# Display_Board.net
KiCad netlist of a schematic drawn in EAGLE
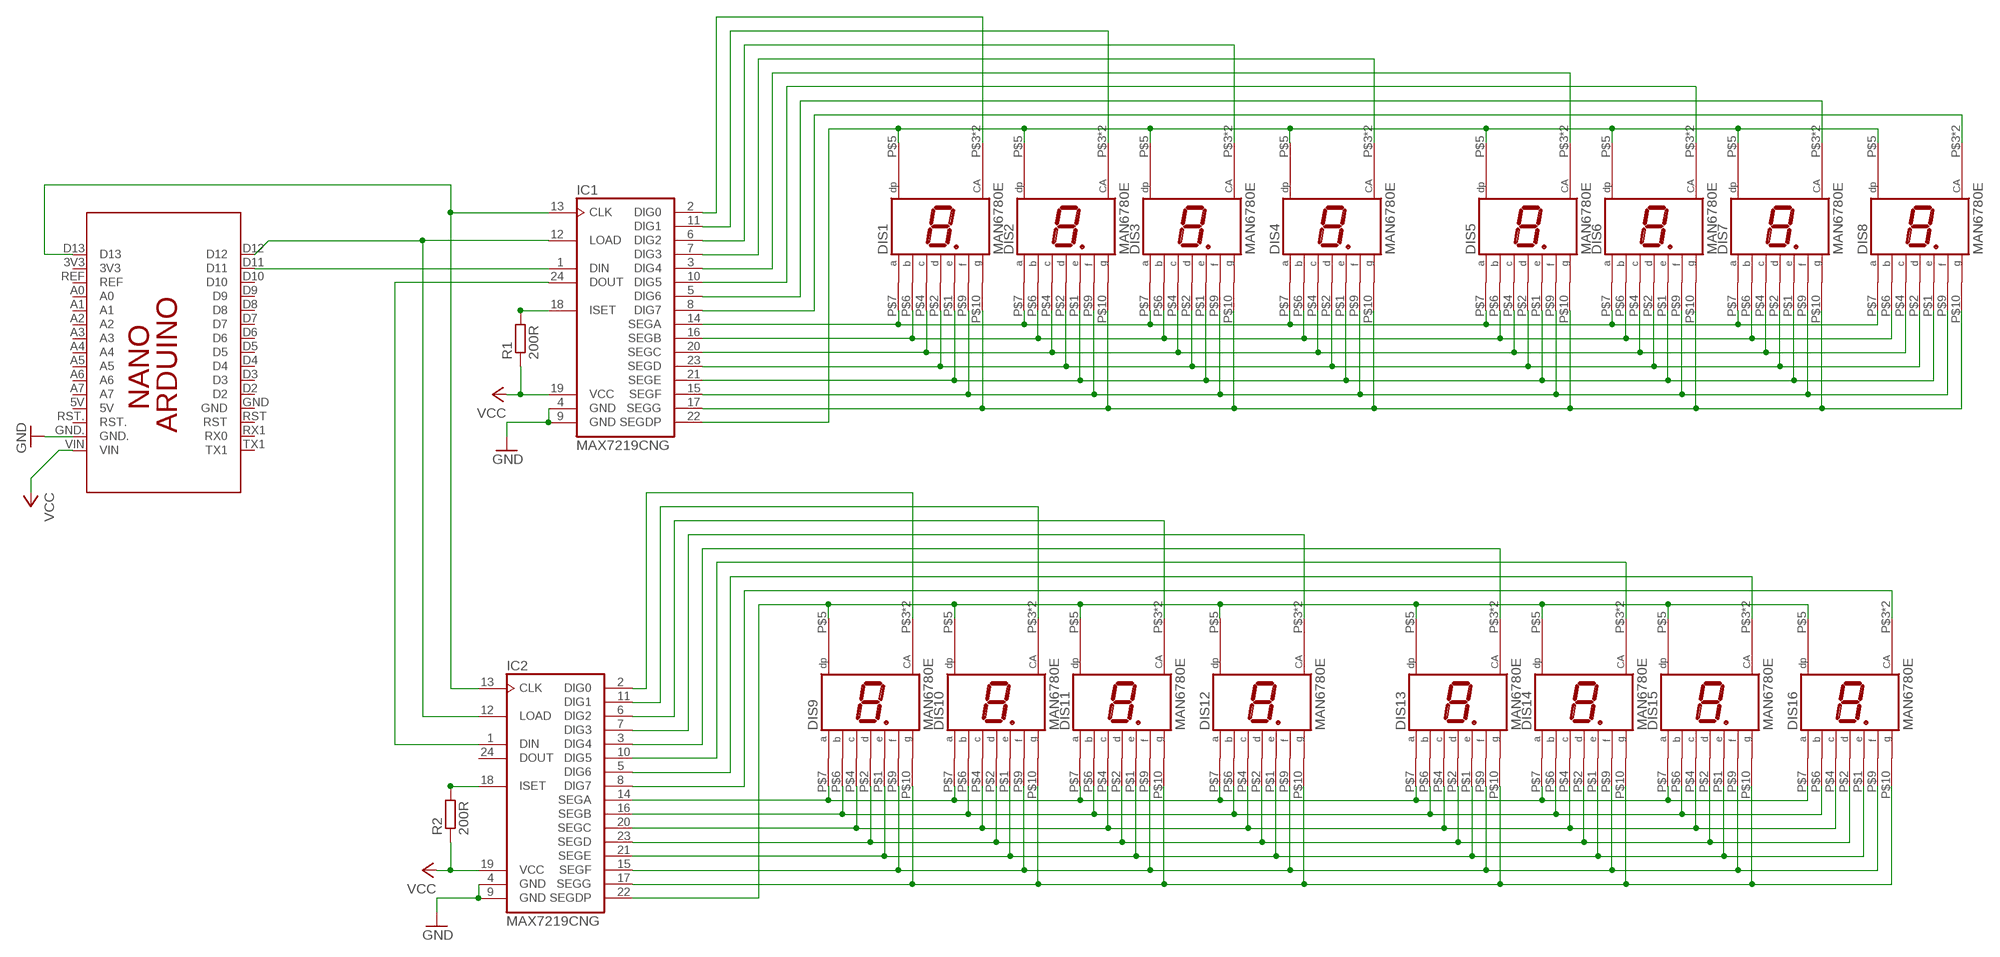
[diagram p0: schematic, sheet 1]

(export (version "E")
  (design (tool "Eeschema 10.0.6"))
  (components
    (comp (ref "DIS1")
      (value "MAN6780E")
      (footprint "eagle-import:MAN6780")
      (libsource (lib "eagle-import") (part "MAN6780E"))
    )
    (comp (ref "DIS2")
      (value "MAN6780E")
      (footprint "eagle-import:MAN6780")
      (libsource (lib "eagle-import") (part "MAN6780E"))
    )
    (comp (ref "DIS3")
      (value "MAN6780E")
      (footprint "eagle-import:MAN6780")
      (libsource (lib "eagle-import") (part "MAN6780E"))
    )
    (comp (ref "DIS4")
      (value "MAN6780E")
      (footprint "eagle-import:MAN6780")
      (libsource (lib "eagle-import") (part "MAN6780E"))
    )
    (comp (ref "DIS5")
      (value "MAN6780E")
      (footprint "eagle-import:MAN6780")
      (libsource (lib "eagle-import") (part "MAN6780E"))
    )
    (comp (ref "DIS6")
      (value "MAN6780E")
      (footprint "eagle-import:MAN6780")
      (libsource (lib "eagle-import") (part "MAN6780E"))
    )
    (comp (ref "DIS7")
      (value "MAN6780E")
      (footprint "eagle-import:MAN6780")
      (libsource (lib "eagle-import") (part "MAN6780E"))
    )
    (comp (ref "DIS8")
      (value "MAN6780E")
      (footprint "eagle-import:MAN6780")
      (libsource (lib "eagle-import") (part "MAN6780E"))
    )
    (comp (ref "DIS9")
      (value "MAN6780E")
      (footprint "eagle-import:MAN6780")
      (libsource (lib "eagle-import") (part "MAN6780E"))
    )
    (comp (ref "DIS10")
      (value "MAN6780E")
      (footprint "eagle-import:MAN6780")
      (libsource (lib "eagle-import") (part "MAN6780E"))
    )
    (comp (ref "DIS11")
      (value "MAN6780E")
      (footprint "eagle-import:MAN6780")
      (libsource (lib "eagle-import") (part "MAN6780E"))
    )
    (comp (ref "DIS12")
      (value "MAN6780E")
      (footprint "eagle-import:MAN6780")
      (libsource (lib "eagle-import") (part "MAN6780E"))
    )
    (comp (ref "DIS13")
      (value "MAN6780E")
      (footprint "eagle-import:MAN6780")
      (libsource (lib "eagle-import") (part "MAN6780E"))
    )
    (comp (ref "DIS14")
      (value "MAN6780E")
      (footprint "eagle-import:MAN6780")
      (libsource (lib "eagle-import") (part "MAN6780E"))
    )
    (comp (ref "DIS15")
      (value "MAN6780E")
      (footprint "eagle-import:MAN6780")
      (libsource (lib "eagle-import") (part "MAN6780E"))
    )
    (comp (ref "DIS16")
      (value "MAN6780E")
      (footprint "eagle-import:MAN6780")
      (libsource (lib "eagle-import") (part "MAN6780E"))
    )
    (comp (ref "IC1")
      (value "MAX7219CNG")
      (footprint "eagle-import:DIL24-3")
      (fields (field (name "MF") "MAXIM"))
      (libsource (lib "eagle-import") (part "MAX7219CNG"))
    )
    (comp (ref "IC2")
      (value "MAX7219CNG")
      (footprint "eagle-import:DIL24-3")
      (fields (field (name "MF") "MAXIM"))
      (libsource (lib "eagle-import") (part "MAX7219CNG"))
    )
    (comp (ref "PCB1")
      (value "ARDUINO_NANO")
      (footprint "eagle-import:ARDUINO_NANO")
      (libsource (lib "eagle-import") (part "ARDUINO_NANO"))
    )
    (comp (ref "R1")
      (value "200R")
      (footprint "eagle-import:M1206")
      (libsource (lib "eagle-import") (part "R-EU_M1206"))
    )
    (comp (ref "R2")
      (value "200R")
      (footprint "eagle-import:M1206")
      (libsource (lib "eagle-import") (part "R-EU_M1206"))
    )
  )
  (nets
    (net (code "1") (name "GND") (class "Default")
      (node (ref "IC1") (pin "4") (pinfunction "GND_4") (pintype "power_in"))
      (node (ref "IC1") (pin "9") (pinfunction "GND_9") (pintype "power_in"))
      (node (ref "IC2") (pin "4") (pinfunction "GND_4") (pintype "power_in"))
      (node (ref "IC2") (pin "9") (pinfunction "GND_9") (pintype "power_in"))
      (node (ref "PCB1") (pin "GND.") (pinfunction "GND._GND.") (pintype "bidirectional"))
    )
    (net (code "2") (name "Net-(DIS1-A)") (class "Default")
      (node (ref "DIS1") (pin "P$7") (pinfunction "A_P$7") (pintype "passive"))
      (node (ref "DIS2") (pin "P$7") (pinfunction "A_P$7") (pintype "passive"))
      (node (ref "DIS3") (pin "P$7") (pinfunction "A_P$7") (pintype "passive"))
      (node (ref "DIS4") (pin "P$7") (pinfunction "A_P$7") (pintype "passive"))
      (node (ref "DIS5") (pin "P$7") (pinfunction "A_P$7") (pintype "passive"))
      (node (ref "DIS6") (pin "P$7") (pinfunction "A_P$7") (pintype "passive"))
      (node (ref "DIS7") (pin "P$7") (pinfunction "A_P$7") (pintype "passive"))
      (node (ref "DIS8") (pin "P$7") (pinfunction "A_P$7") (pintype "passive"))
      (node (ref "IC1") (pin "14") (pinfunction "SEGA_14") (pintype "output"))
    )
    (net (code "3") (name "Net-(DIS1-B)") (class "Default")
      (node (ref "DIS1") (pin "P$6") (pinfunction "B_P$6") (pintype "passive"))
      (node (ref "DIS2") (pin "P$6") (pinfunction "B_P$6") (pintype "passive"))
      (node (ref "DIS3") (pin "P$6") (pinfunction "B_P$6") (pintype "passive"))
      (node (ref "DIS4") (pin "P$6") (pinfunction "B_P$6") (pintype "passive"))
      (node (ref "DIS5") (pin "P$6") (pinfunction "B_P$6") (pintype "passive"))
      (node (ref "DIS6") (pin "P$6") (pinfunction "B_P$6") (pintype "passive"))
      (node (ref "DIS7") (pin "P$6") (pinfunction "B_P$6") (pintype "passive"))
      (node (ref "DIS8") (pin "P$6") (pinfunction "B_P$6") (pintype "passive"))
      (node (ref "IC1") (pin "16") (pinfunction "SEGB_16") (pintype "output"))
    )
    (net (code "4") (name "Net-(DIS1-C)") (class "Default")
      (node (ref "DIS1") (pin "P$4") (pinfunction "C_P$4") (pintype "passive"))
      (node (ref "DIS2") (pin "P$4") (pinfunction "C_P$4") (pintype "passive"))
      (node (ref "DIS3") (pin "P$4") (pinfunction "C_P$4") (pintype "passive"))
      (node (ref "DIS4") (pin "P$4") (pinfunction "C_P$4") (pintype "passive"))
      (node (ref "DIS5") (pin "P$4") (pinfunction "C_P$4") (pintype "passive"))
      (node (ref "DIS6") (pin "P$4") (pinfunction "C_P$4") (pintype "passive"))
      (node (ref "DIS7") (pin "P$4") (pinfunction "C_P$4") (pintype "passive"))
      (node (ref "DIS8") (pin "P$4") (pinfunction "C_P$4") (pintype "passive"))
      (node (ref "IC1") (pin "20") (pinfunction "SEGC_20") (pintype "output"))
    )
    (net (code "5") (name "Net-(DIS1-D)") (class "Default")
      (node (ref "DIS1") (pin "P$2") (pinfunction "D_P$2") (pintype "passive"))
      (node (ref "DIS2") (pin "P$2") (pinfunction "D_P$2") (pintype "passive"))
      (node (ref "DIS3") (pin "P$2") (pinfunction "D_P$2") (pintype "passive"))
      (node (ref "DIS4") (pin "P$2") (pinfunction "D_P$2") (pintype "passive"))
      (node (ref "DIS5") (pin "P$2") (pinfunction "D_P$2") (pintype "passive"))
      (node (ref "DIS6") (pin "P$2") (pinfunction "D_P$2") (pintype "passive"))
      (node (ref "DIS7") (pin "P$2") (pinfunction "D_P$2") (pintype "passive"))
      (node (ref "DIS8") (pin "P$2") (pinfunction "D_P$2") (pintype "passive"))
      (node (ref "IC1") (pin "23") (pinfunction "SEGD_23") (pintype "output"))
    )
    (net (code "6") (name "Net-(DIS1-DP)") (class "Default")
      (node (ref "DIS1") (pin "P$5") (pinfunction "DP_P$5") (pintype "passive"))
      (node (ref "DIS2") (pin "P$5") (pinfunction "DP_P$5") (pintype "passive"))
      (node (ref "DIS3") (pin "P$5") (pinfunction "DP_P$5") (pintype "passive"))
      (node (ref "DIS4") (pin "P$5") (pinfunction "DP_P$5") (pintype "passive"))
      (node (ref "DIS5") (pin "P$5") (pinfunction "DP_P$5") (pintype "passive"))
      (node (ref "DIS6") (pin "P$5") (pinfunction "DP_P$5") (pintype "passive"))
      (node (ref "DIS7") (pin "P$5") (pinfunction "DP_P$5") (pintype "passive"))
      (node (ref "DIS8") (pin "P$5") (pinfunction "DP_P$5") (pintype "passive"))
      (node (ref "IC1") (pin "22") (pinfunction "SEGDP_22") (pintype "output"))
    )
    (net (code "7") (name "Net-(DIS1-E)") (class "Default")
      (node (ref "DIS1") (pin "P$1") (pinfunction "E_P$1") (pintype "passive"))
      (node (ref "DIS2") (pin "P$1") (pinfunction "E_P$1") (pintype "passive"))
      (node (ref "DIS3") (pin "P$1") (pinfunction "E_P$1") (pintype "passive"))
      (node (ref "DIS4") (pin "P$1") (pinfunction "E_P$1") (pintype "passive"))
      (node (ref "DIS5") (pin "P$1") (pinfunction "E_P$1") (pintype "passive"))
      (node (ref "DIS6") (pin "P$1") (pinfunction "E_P$1") (pintype "passive"))
      (node (ref "DIS7") (pin "P$1") (pinfunction "E_P$1") (pintype "passive"))
      (node (ref "DIS8") (pin "P$1") (pinfunction "E_P$1") (pintype "passive"))
      (node (ref "IC1") (pin "21") (pinfunction "SEGE_21") (pintype "output"))
    )
    (net (code "8") (name "Net-(DIS1-F)") (class "Default")
      (node (ref "DIS1") (pin "P$9") (pinfunction "F_P$9") (pintype "passive"))
      (node (ref "DIS2") (pin "P$9") (pinfunction "F_P$9") (pintype "passive"))
      (node (ref "DIS3") (pin "P$9") (pinfunction "F_P$9") (pintype "passive"))
      (node (ref "DIS4") (pin "P$9") (pinfunction "F_P$9") (pintype "passive"))
      (node (ref "DIS5") (pin "P$9") (pinfunction "F_P$9") (pintype "passive"))
      (node (ref "DIS6") (pin "P$9") (pinfunction "F_P$9") (pintype "passive"))
      (node (ref "DIS7") (pin "P$9") (pinfunction "F_P$9") (pintype "passive"))
      (node (ref "DIS8") (pin "P$9") (pinfunction "F_P$9") (pintype "passive"))
      (node (ref "IC1") (pin "15") (pinfunction "SEGF_15") (pintype "output"))
    )
    (net (code "9") (name "Net-(DIS1-G)") (class "Default")
      (node (ref "DIS1") (pin "P$10") (pinfunction "G_P$10") (pintype "passive"))
      (node (ref "DIS2") (pin "P$10") (pinfunction "G_P$10") (pintype "passive"))
      (node (ref "DIS3") (pin "P$10") (pinfunction "G_P$10") (pintype "passive"))
      (node (ref "DIS4") (pin "P$10") (pinfunction "G_P$10") (pintype "passive"))
      (node (ref "DIS5") (pin "P$10") (pinfunction "G_P$10") (pintype "passive"))
      (node (ref "DIS6") (pin "P$10") (pinfunction "G_P$10") (pintype "passive"))
      (node (ref "DIS7") (pin "P$10") (pinfunction "G_P$10") (pintype "passive"))
      (node (ref "DIS8") (pin "P$10") (pinfunction "G_P$10") (pintype "passive"))
      (node (ref "IC1") (pin "17") (pinfunction "SEGG_17") (pintype "output"))
    )
    (net (code "10") (name "Net-(DIS10-A)") (class "Default")
      (node (ref "DIS10") (pin "P$7") (pinfunction "A_P$7") (pintype "passive"))
      (node (ref "DIS11") (pin "P$7") (pinfunction "A_P$7") (pintype "passive"))
      (node (ref "DIS12") (pin "P$7") (pinfunction "A_P$7") (pintype "passive"))
      (node (ref "DIS13") (pin "P$7") (pinfunction "A_P$7") (pintype "passive"))
      (node (ref "DIS14") (pin "P$7") (pinfunction "A_P$7") (pintype "passive"))
      (node (ref "DIS15") (pin "P$7") (pinfunction "A_P$7") (pintype "passive"))
      (node (ref "DIS16") (pin "P$7") (pinfunction "A_P$7") (pintype "passive"))
      (node (ref "DIS9") (pin "P$7") (pinfunction "A_P$7") (pintype "passive"))
      (node (ref "IC2") (pin "14") (pinfunction "SEGA_14") (pintype "output"))
    )
    (net (code "11") (name "Net-(DIS10-B)") (class "Default")
      (node (ref "DIS10") (pin "P$6") (pinfunction "B_P$6") (pintype "passive"))
      (node (ref "DIS11") (pin "P$6") (pinfunction "B_P$6") (pintype "passive"))
      (node (ref "DIS12") (pin "P$6") (pinfunction "B_P$6") (pintype "passive"))
      (node (ref "DIS13") (pin "P$6") (pinfunction "B_P$6") (pintype "passive"))
      (node (ref "DIS14") (pin "P$6") (pinfunction "B_P$6") (pintype "passive"))
      (node (ref "DIS15") (pin "P$6") (pinfunction "B_P$6") (pintype "passive"))
      (node (ref "DIS16") (pin "P$6") (pinfunction "B_P$6") (pintype "passive"))
      (node (ref "DIS9") (pin "P$6") (pinfunction "B_P$6") (pintype "passive"))
      (node (ref "IC2") (pin "16") (pinfunction "SEGB_16") (pintype "output"))
    )
    (net (code "12") (name "Net-(DIS10-C)") (class "Default")
      (node (ref "DIS10") (pin "P$4") (pinfunction "C_P$4") (pintype "passive"))
      (node (ref "DIS11") (pin "P$4") (pinfunction "C_P$4") (pintype "passive"))
      (node (ref "DIS12") (pin "P$4") (pinfunction "C_P$4") (pintype "passive"))
      (node (ref "DIS13") (pin "P$4") (pinfunction "C_P$4") (pintype "passive"))
      (node (ref "DIS14") (pin "P$4") (pinfunction "C_P$4") (pintype "passive"))
      (node (ref "DIS15") (pin "P$4") (pinfunction "C_P$4") (pintype "passive"))
      (node (ref "DIS16") (pin "P$4") (pinfunction "C_P$4") (pintype "passive"))
      (node (ref "DIS9") (pin "P$4") (pinfunction "C_P$4") (pintype "passive"))
      (node (ref "IC2") (pin "20") (pinfunction "SEGC_20") (pintype "output"))
    )
    (net (code "13") (name "Net-(DIS10-D)") (class "Default")
      (node (ref "DIS10") (pin "P$2") (pinfunction "D_P$2") (pintype "passive"))
      (node (ref "DIS11") (pin "P$2") (pinfunction "D_P$2") (pintype "passive"))
      (node (ref "DIS12") (pin "P$2") (pinfunction "D_P$2") (pintype "passive"))
      (node (ref "DIS13") (pin "P$2") (pinfunction "D_P$2") (pintype "passive"))
      (node (ref "DIS14") (pin "P$2") (pinfunction "D_P$2") (pintype "passive"))
      (node (ref "DIS15") (pin "P$2") (pinfunction "D_P$2") (pintype "passive"))
      (node (ref "DIS16") (pin "P$2") (pinfunction "D_P$2") (pintype "passive"))
      (node (ref "DIS9") (pin "P$2") (pinfunction "D_P$2") (pintype "passive"))
      (node (ref "IC2") (pin "23") (pinfunction "SEGD_23") (pintype "output"))
    )
    (net (code "14") (name "Net-(DIS10-DP)") (class "Default")
      (node (ref "DIS10") (pin "P$5") (pinfunction "DP_P$5") (pintype "passive"))
      (node (ref "DIS11") (pin "P$5") (pinfunction "DP_P$5") (pintype "passive"))
      (node (ref "DIS12") (pin "P$5") (pinfunction "DP_P$5") (pintype "passive"))
      (node (ref "DIS13") (pin "P$5") (pinfunction "DP_P$5") (pintype "passive"))
      (node (ref "DIS14") (pin "P$5") (pinfunction "DP_P$5") (pintype "passive"))
      (node (ref "DIS15") (pin "P$5") (pinfunction "DP_P$5") (pintype "passive"))
      (node (ref "DIS16") (pin "P$5") (pinfunction "DP_P$5") (pintype "passive"))
      (node (ref "DIS9") (pin "P$5") (pinfunction "DP_P$5") (pintype "passive"))
      (node (ref "IC2") (pin "22") (pinfunction "SEGDP_22") (pintype "output"))
    )
    (net (code "15") (name "Net-(DIS10-E)") (class "Default")
      (node (ref "DIS10") (pin "P$1") (pinfunction "E_P$1") (pintype "passive"))
      (node (ref "DIS11") (pin "P$1") (pinfunction "E_P$1") (pintype "passive"))
      (node (ref "DIS12") (pin "P$1") (pinfunction "E_P$1") (pintype "passive"))
      (node (ref "DIS13") (pin "P$1") (pinfunction "E_P$1") (pintype "passive"))
      (node (ref "DIS14") (pin "P$1") (pinfunction "E_P$1") (pintype "passive"))
      (node (ref "DIS15") (pin "P$1") (pinfunction "E_P$1") (pintype "passive"))
      (node (ref "DIS16") (pin "P$1") (pinfunction "E_P$1") (pintype "passive"))
      (node (ref "DIS9") (pin "P$1") (pinfunction "E_P$1") (pintype "passive"))
      (node (ref "IC2") (pin "21") (pinfunction "SEGE_21") (pintype "output"))
    )
    (net (code "16") (name "Net-(DIS10-F)") (class "Default")
      (node (ref "DIS10") (pin "P$9") (pinfunction "F_P$9") (pintype "passive"))
      (node (ref "DIS11") (pin "P$9") (pinfunction "F_P$9") (pintype "passive"))
      (node (ref "DIS12") (pin "P$9") (pinfunction "F_P$9") (pintype "passive"))
      (node (ref "DIS13") (pin "P$9") (pinfunction "F_P$9") (pintype "passive"))
      (node (ref "DIS14") (pin "P$9") (pinfunction "F_P$9") (pintype "passive"))
      (node (ref "DIS15") (pin "P$9") (pinfunction "F_P$9") (pintype "passive"))
      (node (ref "DIS16") (pin "P$9") (pinfunction "F_P$9") (pintype "passive"))
      (node (ref "DIS9") (pin "P$9") (pinfunction "F_P$9") (pintype "passive"))
      (node (ref "IC2") (pin "15") (pinfunction "SEGF_15") (pintype "output"))
    )
    (net (code "17") (name "Net-(DIS10-G)") (class "Default")
      (node (ref "DIS10") (pin "P$10") (pinfunction "G_P$10") (pintype "passive"))
      (node (ref "DIS11") (pin "P$10") (pinfunction "G_P$10") (pintype "passive"))
      (node (ref "DIS12") (pin "P$10") (pinfunction "G_P$10") (pintype "passive"))
      (node (ref "DIS13") (pin "P$10") (pinfunction "G_P$10") (pintype "passive"))
      (node (ref "DIS14") (pin "P$10") (pinfunction "G_P$10") (pintype "passive"))
      (node (ref "DIS15") (pin "P$10") (pinfunction "G_P$10") (pintype "passive"))
      (node (ref "DIS16") (pin "P$10") (pinfunction "G_P$10") (pintype "passive"))
      (node (ref "DIS9") (pin "P$10") (pinfunction "G_P$10") (pintype "passive"))
      (node (ref "IC2") (pin "17") (pinfunction "SEGG_17") (pintype "output"))
    )
    (net (code "18") (name "Net-(IC1-CLK)") (class "Default")
      (node (ref "IC1") (pin "13") (pinfunction "CLK_13") (pintype "input"))
      (node (ref "IC2") (pin "13") (pinfunction "CLK_13") (pintype "input"))
      (node (ref "PCB1") (pin "D13") (pinfunction "D13_D13") (pintype "bidirectional"))
    )
    (net (code "19") (name "Net-(IC1-DIG0)") (class "Default")
      (node (ref "DIS1") (pin "P$3") (pinfunction "CA_P$3") (pintype "passive"))
      (node (ref "DIS1") (pin "P$8") (pinfunction "CA_P$8") (pintype "passive"))
      (node (ref "IC1") (pin "2") (pinfunction "DIG0_2") (pintype "output"))
    )
    (net (code "20") (name "Net-(IC1-DIG1)") (class "Default")
      (node (ref "DIS2") (pin "P$3") (pinfunction "CA_P$3") (pintype "passive"))
      (node (ref "DIS2") (pin "P$8") (pinfunction "CA_P$8") (pintype "passive"))
      (node (ref "IC1") (pin "11") (pinfunction "DIG1_11") (pintype "output"))
    )
    (net (code "21") (name "Net-(IC1-DIG2)") (class "Default")
      (node (ref "DIS3") (pin "P$3") (pinfunction "CA_P$3") (pintype "passive"))
      (node (ref "DIS3") (pin "P$8") (pinfunction "CA_P$8") (pintype "passive"))
      (node (ref "IC1") (pin "6") (pinfunction "DIG2_6") (pintype "output"))
    )
    (net (code "22") (name "Net-(IC1-DIG3)") (class "Default")
      (node (ref "DIS4") (pin "P$3") (pinfunction "CA_P$3") (pintype "passive"))
      (node (ref "DIS4") (pin "P$8") (pinfunction "CA_P$8") (pintype "passive"))
      (node (ref "IC1") (pin "7") (pinfunction "DIG3_7") (pintype "output"))
    )
    (net (code "23") (name "Net-(IC1-DIG4)") (class "Default")
      (node (ref "DIS5") (pin "P$3") (pinfunction "CA_P$3") (pintype "passive"))
      (node (ref "DIS5") (pin "P$8") (pinfunction "CA_P$8") (pintype "passive"))
      (node (ref "IC1") (pin "3") (pinfunction "DIG4_3") (pintype "output"))
    )
    (net (code "24") (name "Net-(IC1-DIG5)") (class "Default")
      (node (ref "DIS6") (pin "P$3") (pinfunction "CA_P$3") (pintype "passive"))
      (node (ref "DIS6") (pin "P$8") (pinfunction "CA_P$8") (pintype "passive"))
      (node (ref "IC1") (pin "10") (pinfunction "DIG5_10") (pintype "output"))
    )
    (net (code "25") (name "Net-(IC1-DIG6)") (class "Default")
      (node (ref "DIS7") (pin "P$3") (pinfunction "CA_P$3") (pintype "passive"))
      (node (ref "DIS7") (pin "P$8") (pinfunction "CA_P$8") (pintype "passive"))
      (node (ref "IC1") (pin "5") (pinfunction "DIG6_5") (pintype "output"))
    )
    (net (code "26") (name "Net-(IC1-DIG7)") (class "Default")
      (node (ref "DIS8") (pin "P$3") (pinfunction "CA_P$3") (pintype "passive"))
      (node (ref "DIS8") (pin "P$8") (pinfunction "CA_P$8") (pintype "passive"))
      (node (ref "IC1") (pin "8") (pinfunction "DIG7_8") (pintype "output"))
    )
    (net (code "27") (name "Net-(IC1-DIN)") (class "Default")
      (node (ref "IC1") (pin "1") (pinfunction "DIN_1") (pintype "input"))
      (node (ref "PCB1") (pin "D11") (pinfunction "D11_D11") (pintype "bidirectional"))
    )
    (net (code "28") (name "Net-(IC1-DOUT)") (class "Default")
      (node (ref "IC1") (pin "24") (pinfunction "DOUT_24") (pintype "output"))
      (node (ref "IC2") (pin "1") (pinfunction "DIN_1") (pintype "input"))
    )
    (net (code "29") (name "Net-(IC1-ISET)") (class "Default")
      (node (ref "IC1") (pin "18") (pinfunction "ISET_18") (pintype "input"))
      (node (ref "R1") (pin "2") (pinfunction "2_2") (pintype "passive"))
    )
    (net (code "30") (name "Net-(IC1-LOAD)") (class "Default")
      (node (ref "IC1") (pin "12") (pinfunction "LOAD_12") (pintype "input"))
      (node (ref "IC2") (pin "12") (pinfunction "LOAD_12") (pintype "input"))
      (node (ref "PCB1") (pin "D12") (pinfunction "D12_D12") (pintype "bidirectional"))
    )
    (net (code "31") (name "Net-(IC2-DIG0)") (class "Default")
      (node (ref "DIS9") (pin "P$3") (pinfunction "CA_P$3") (pintype "passive"))
      (node (ref "DIS9") (pin "P$8") (pinfunction "CA_P$8") (pintype "passive"))
      (node (ref "IC2") (pin "2") (pinfunction "DIG0_2") (pintype "output"))
    )
    (net (code "32") (name "Net-(IC2-DIG1)") (class "Default")
      (node (ref "DIS10") (pin "P$3") (pinfunction "CA_P$3") (pintype "passive"))
      (node (ref "DIS10") (pin "P$8") (pinfunction "CA_P$8") (pintype "passive"))
      (node (ref "IC2") (pin "11") (pinfunction "DIG1_11") (pintype "output"))
    )
    (net (code "33") (name "Net-(IC2-DIG2)") (class "Default")
      (node (ref "DIS11") (pin "P$3") (pinfunction "CA_P$3") (pintype "passive"))
      (node (ref "DIS11") (pin "P$8") (pinfunction "CA_P$8") (pintype "passive"))
      (node (ref "IC2") (pin "6") (pinfunction "DIG2_6") (pintype "output"))
    )
    (net (code "34") (name "Net-(IC2-DIG3)") (class "Default")
      (node (ref "DIS12") (pin "P$3") (pinfunction "CA_P$3") (pintype "passive"))
      (node (ref "DIS12") (pin "P$8") (pinfunction "CA_P$8") (pintype "passive"))
      (node (ref "IC2") (pin "7") (pinfunction "DIG3_7") (pintype "output"))
    )
    (net (code "35") (name "Net-(IC2-DIG4)") (class "Default")
      (node (ref "DIS13") (pin "P$3") (pinfunction "CA_P$3") (pintype "passive"))
      (node (ref "DIS13") (pin "P$8") (pinfunction "CA_P$8") (pintype "passive"))
      (node (ref "IC2") (pin "3") (pinfunction "DIG4_3") (pintype "output"))
    )
    (net (code "36") (name "Net-(IC2-DIG5)") (class "Default")
      (node (ref "DIS14") (pin "P$3") (pinfunction "CA_P$3") (pintype "passive"))
      (node (ref "DIS14") (pin "P$8") (pinfunction "CA_P$8") (pintype "passive"))
      (node (ref "IC2") (pin "10") (pinfunction "DIG5_10") (pintype "output"))
    )
    (net (code "37") (name "Net-(IC2-DIG6)") (class "Default")
      (node (ref "DIS15") (pin "P$3") (pinfunction "CA_P$3") (pintype "passive"))
      (node (ref "DIS15") (pin "P$8") (pinfunction "CA_P$8") (pintype "passive"))
      (node (ref "IC2") (pin "5") (pinfunction "DIG6_5") (pintype "output"))
    )
    (net (code "38") (name "Net-(IC2-DIG7)") (class "Default")
      (node (ref "DIS16") (pin "P$3") (pinfunction "CA_P$3") (pintype "passive"))
      (node (ref "DIS16") (pin "P$8") (pinfunction "CA_P$8") (pintype "passive"))
      (node (ref "IC2") (pin "8") (pinfunction "DIG7_8") (pintype "output"))
    )
    (net (code "39") (name "Net-(IC2-ISET)") (class "Default")
      (node (ref "IC2") (pin "18") (pinfunction "ISET_18") (pintype "input"))
      (node (ref "R2") (pin "2") (pinfunction "2_2") (pintype "passive"))
    )
    (net (code "40") (name "VCC") (class "Default")
      (node (ref "IC1") (pin "19") (pinfunction "VCC_19") (pintype "power_in"))
      (node (ref "IC2") (pin "19") (pinfunction "VCC_19") (pintype "power_in"))
      (node (ref "PCB1") (pin "VIN") (pinfunction "VIN_VIN") (pintype "bidirectional"))
      (node (ref "R1") (pin "1") (pinfunction "1_1") (pintype "passive"))
      (node (ref "R2") (pin "1") (pinfunction "1_1") (pintype "passive"))
    )
    (net (code "41") (name "unconnected-(IC2-DOUT-Pad24)") (class "Default")
      (node (ref "IC2") (pin "24") (pinfunction "DOUT_24") (pintype "output"))
    )
    (net (code "42") (name "unconnected-(PCB1-Pad3V3)") (class "Default")
      (node (ref "PCB1") (pin "3V3") (pinfunction "3V3_3V3") (pintype "bidirectional"))
    )
    (net (code "43") (name "unconnected-(PCB1-Pad5V)") (class "Default")
      (node (ref "PCB1") (pin "5V") (pinfunction "5V_5V") (pintype "bidirectional"))
    )
    (net (code "44") (name "unconnected-(PCB1-PadA0)") (class "Default")
      (node (ref "PCB1") (pin "A0") (pinfunction "A0_A0") (pintype "bidirectional"))
    )
    (net (code "45") (name "unconnected-(PCB1-PadA1)") (class "Default")
      (node (ref "PCB1") (pin "A1") (pinfunction "A1_A1") (pintype "bidirectional"))
    )
    (net (code "46") (name "unconnected-(PCB1-PadA2)") (class "Default")
      (node (ref "PCB1") (pin "A2") (pinfunction "A2_A2") (pintype "bidirectional"))
    )
    (net (code "47") (name "unconnected-(PCB1-PadA3)") (class "Default")
      (node (ref "PCB1") (pin "A3") (pinfunction "A3_A3") (pintype "bidirectional"))
    )
    (net (code "48") (name "unconnected-(PCB1-PadA4)") (class "Default")
      (node (ref "PCB1") (pin "A4") (pinfunction "A4_A4") (pintype "bidirectional"))
    )
    (net (code "49") (name "unconnected-(PCB1-PadA5)") (class "Default")
      (node (ref "PCB1") (pin "A5") (pinfunction "A5_A5") (pintype "bidirectional"))
    )
    (net (code "50") (name "unconnected-(PCB1-PadA6)") (class "Default")
      (node (ref "PCB1") (pin "A6") (pinfunction "A6_A6") (pintype "bidirectional"))
    )
    (net (code "51") (name "unconnected-(PCB1-PadA7)") (class "Default")
      (node (ref "PCB1") (pin "A7") (pinfunction "A7_A7") (pintype "bidirectional"))
    )
    (net (code "52") (name "unconnected-(PCB1-PadD2)") (class "Default")
      (node (ref "PCB1") (pin "D2") (pinfunction "D2_D2") (pintype "bidirectional"))
    )
    (net (code "53") (name "unconnected-(PCB1-PadD3)") (class "Default")
      (node (ref "PCB1") (pin "D3") (pinfunction "D3_D3") (pintype "bidirectional"))
    )
    (net (code "54") (name "unconnected-(PCB1-PadD4)") (class "Default")
      (node (ref "PCB1") (pin "D4") (pinfunction "D4_D4") (pintype "bidirectional"))
    )
    (net (code "55") (name "unconnected-(PCB1-PadD5)") (class "Default")
      (node (ref "PCB1") (pin "D5") (pinfunction "D5_D5") (pintype "bidirectional"))
    )
    (net (code "56") (name "unconnected-(PCB1-PadD6)") (class "Default")
      (node (ref "PCB1") (pin "D6") (pinfunction "D6_D6") (pintype "bidirectional"))
    )
    (net (code "57") (name "unconnected-(PCB1-PadD7)") (class "Default")
      (node (ref "PCB1") (pin "D7") (pinfunction "D7_D7") (pintype "bidirectional"))
    )
    (net (code "58") (name "unconnected-(PCB1-PadD8)") (class "Default")
      (node (ref "PCB1") (pin "D8") (pinfunction "D8_D8") (pintype "bidirectional"))
    )
    (net (code "59") (name "unconnected-(PCB1-PadD9)") (class "Default")
      (node (ref "PCB1") (pin "D9") (pinfunction "D9_D9") (pintype "bidirectional"))
    )
    (net (code "60") (name "unconnected-(PCB1-PadD10)") (class "Default")
      (node (ref "PCB1") (pin "D10") (pinfunction "D10_D10") (pintype "bidirectional"))
    )
    (net (code "61") (name "unconnected-(PCB1-PadGND)") (class "Default")
      (node (ref "PCB1") (pin "GND") (pinfunction "GND_GND") (pintype "bidirectional"))
    )
    (net (code "62") (name "unconnected-(PCB1-PadREF)") (class "Default")
      (node (ref "PCB1") (pin "REF") (pinfunction "REF_REF") (pintype "bidirectional"))
    )
    (net (code "63") (name "unconnected-(PCB1-PadRST)") (class "Default")
      (node (ref "PCB1") (pin "RST") (pinfunction "RST_RST") (pintype "bidirectional"))
    )
    (net (code "64") (name "unconnected-(PCB1-PadRST.)") (class "Default")
      (node (ref "PCB1") (pin "RST.") (pinfunction "RST._RST.") (pintype "bidirectional"))
    )
    (net (code "65") (name "unconnected-(PCB1-PadTX1)") (class "Default")
      (node (ref "PCB1") (pin "TX1") (pinfunction "TX1_TX1") (pintype "bidirectional"))
    )
    (net (code "66") (name "unconnected-(PCB1-RX0-PadRX1)") (class "Default")
      (node (ref "PCB1") (pin "RX1") (pinfunction "RX0_RX1") (pintype "bidirectional"))
    )
  )
)
